# MCU.net
KiCad netlist of a schematic drawn in Altium Designer
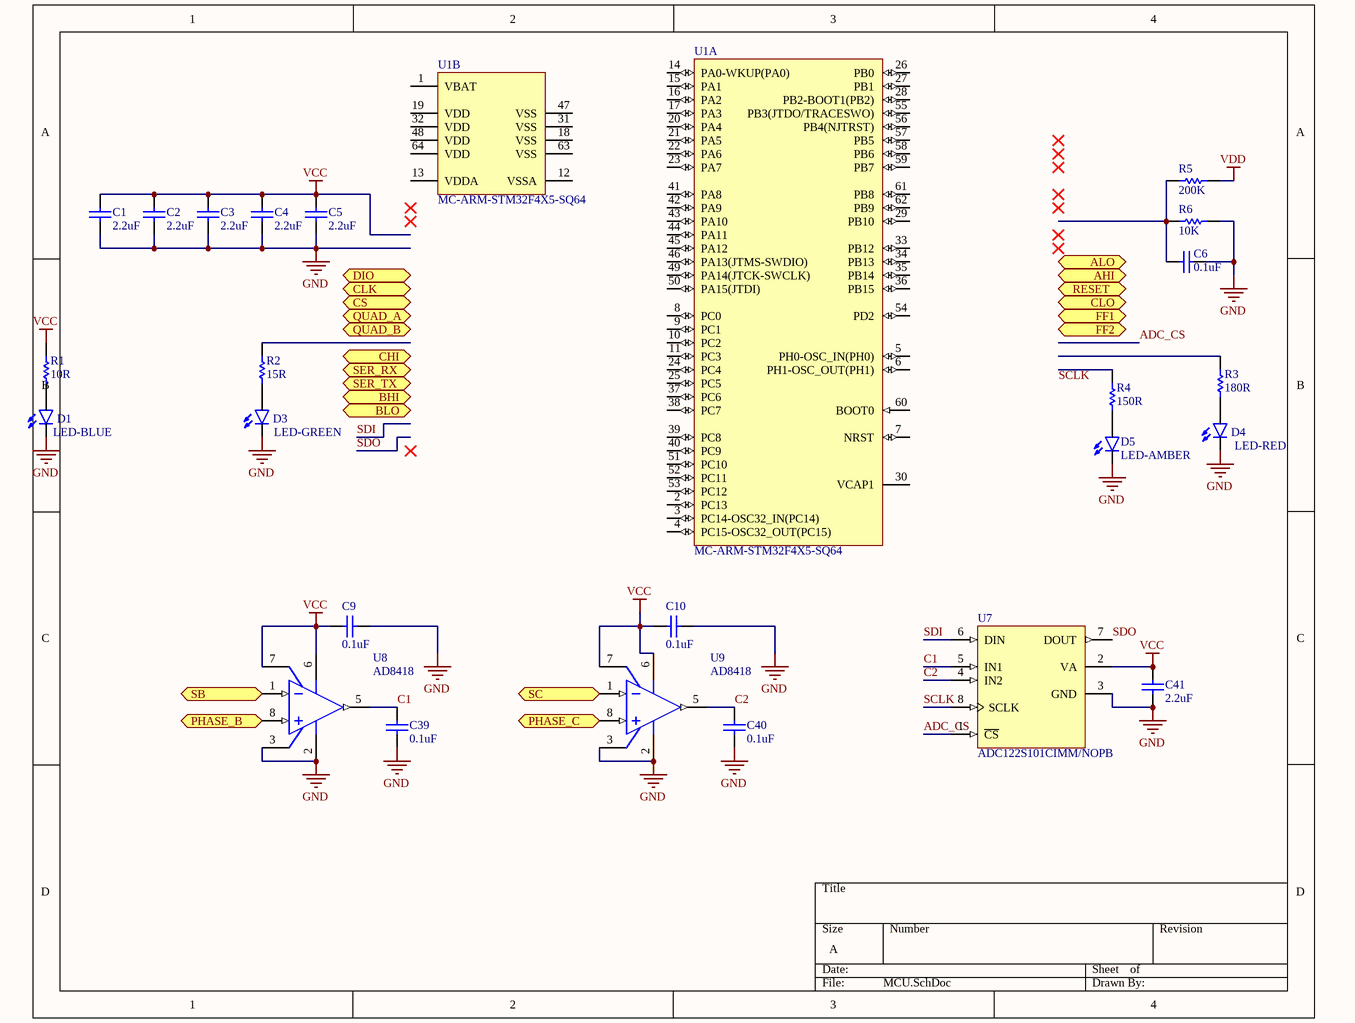
[diagram p0: MCU.SchDoc]

(export (version "E")
  (design (tool "Eeschema 10.0.6"))
  (components
    (comp (ref "C1")
      (value "2.2uF")
      (footprint "CAPC0603(1608)55_N")
      (description "CAP 2.2uF 16V Â±10% 0603 (1608 Metric) Thickness 0.55mm SMD")
      (fields (field (name "TOLERANCE") "Â±10%"))
      (libsource (lib "Altium Content Vault") (part "CMP-1035-02762-1"))
    )
    (comp (ref "C2")
      (value "2.2uF")
      (footprint "CAPC0603(1608)55_N")
      (description "CAP 2.2uF 16V Â±10% 0603 (1608 Metric) Thickness 0.55mm SMD")
      (fields (field (name "TOLERANCE") "Â±10%"))
      (libsource (lib "Altium Content Vault") (part "CMP-1035-02762-1"))
    )
    (comp (ref "C3")
      (value "2.2uF")
      (footprint "CAPC0603(1608)55_N")
      (description "CAP 2.2uF 16V Â±10% 0603 (1608 Metric) Thickness 0.55mm SMD")
      (fields (field (name "TOLERANCE") "Â±10%"))
      (libsource (lib "Altium Content Vault") (part "CMP-1035-02762-1"))
    )
    (comp (ref "C4")
      (value "2.2uF")
      (footprint "CAPC0603(1608)55_N")
      (description "CAP 2.2uF 16V Â±10% 0603 (1608 Metric) Thickness 0.55mm SMD")
      (fields (field (name "TOLERANCE") "Â±10%"))
      (libsource (lib "Altium Content Vault") (part "CMP-1035-02762-1"))
    )
    (comp (ref "C5")
      (value "2.2uF")
      (footprint "CAPC0603(1608)55_N")
      (description "CAP 2.2uF 16V Â±10% 0603 (1608 Metric) Thickness 0.55mm SMD")
      (fields (field (name "TOLERANCE") "Â±10%"))
      (libsource (lib "Altium Content Vault") (part "CMP-1035-02762-1"))
    )
    (comp (ref "C6")
      (value "0.1uF")
      (footprint "CAPC0603(1608)100_L")
      (description "CAP 100nF 50V Â±5% 0603 (1608 Metric) Thickness 1mm SMD")
      (fields (field (name "TOLERANCE") "Â±5%"))
      (libsource (lib "Altium Content Vault") (part "CMP-1035-02591-1"))
    )
    (comp (ref "C9")
      (value "0.1uF")
      (footprint "CAPC0603(1608)100_L")
      (description "CAP 100nF 6.3V Â±20% 0603 (1608 Metric) Thickness 1mm SMD")
      (fields (field (name "TOLERANCE") "Â±20%"))
      (libsource (lib "Altium Content Vault") (part "CMP-1035-02577-1"))
    )
    (comp (ref "C10")
      (value "0.1uF")
      (footprint "CAPC0603(1608)100_L")
      (description "CAP 100nF 6.3V Â±20% 0603 (1608 Metric) Thickness 1mm SMD")
      (fields (field (name "TOLERANCE") "Â±20%"))
      (libsource (lib "Altium Content Vault") (part "CMP-1035-02577-1"))
    )
    (comp (ref "C39")
      (value "0.1uF")
      (footprint "CAPC0603(1608)100_M")
      (description "CAP 100nF 6.3V ±5% 0603 (1608 Metric) Thickness 1mm SMD")
      (fields (field (name "TOLERANCE") "Â±5%"))
      (libsource (lib "Altium Content Vault") (part "CAP"))
    )
    (comp (ref "C40")
      (value "0.1uF")
      (footprint "CAPC0603(1608)100_M")
      (description "CAP 100nF 6.3V ±5% 0603 (1608 Metric) Thickness 1mm SMD")
      (fields (field (name "TOLERANCE") "Â±5%"))
      (libsource (lib "Altium Content Vault") (part "CAP"))
    )
    (comp (ref "C41")
      (value "2.2uF")
      (footprint "CAPC0603(1608)100_L")
      (description "CAP 2.2uF 6.3V ±10% 0603 (1608 Metric) Thickness 1mm SMD")
      (fields (field (name "TOLERANCE") "Â±10%"))
      (libsource (lib "Altium Content Vault") (part "CAP"))
    )
    (comp (ref "D1")
      (value "LED-BLUE")
      (footprint "LED-1206")
      (libsource (lib "Components") (part "LED-BLUE1206"))
    )
    (comp (ref "D3")
      (value "LED-GREEN")
      (footprint "LED-1206")
      (libsource (lib "Components") (part "LED-GREEN1206"))
    )
    (comp (ref "D4")
      (value "LED-RED")
      (footprint "LED-1206")
      (libsource (lib "Components") (part "LED-RED1206"))
    )
    (comp (ref "D5")
      (value "LED-AMBER")
      (footprint "LED-1206")
      (libsource (lib "Components") (part "LED-AMBER1206"))
    )
    (comp (ref "R1")
      (value "10R")
      (footprint "RESC0603(1608)_N")
      (description "10R 0.1W 5% 0603 (1608 Metric)  SMD")
      (fields (field (name "TOLERANCE") "5 %") (field (name "POWER") "0.1 W"))
      (libsource (lib "Altium Content Vault") (part "CMP-1012-00026-1"))
    )
    (comp (ref "R2")
      (value "15R")
      (footprint "RESC0603(1608)_N")
      (description "15R 0.1W 5% 0603 (1608 Metric)  SMD")
      (fields (field (name "TOLERANCE") "5 %") (field (name "POWER") "0.1 W"))
      (libsource (lib "Altium Content Vault") (part "CMP-1012-00030-1"))
    )
    (comp (ref "R3")
      (value "180R")
      (footprint "RESC0603(1608)_N")
      (description "180R 0.1W 5% 0603 (1608 Metric)  SMD")
      (fields (field (name "POWER") "0.1 W") (field (name "TOLERANCE") "5 %"))
      (libsource (lib "Altium Content Vault") (part "CMP-1012-00056-1"))
    )
    (comp (ref "R4")
      (value "150R")
      (footprint "RESC0603(1608)_N")
      (description "150R 0.1W 5% 0603 (1608 Metric)  SMD")
      (fields (field (name "POWER") "0.1 W") (field (name "TOLERANCE") "5 %"))
      (libsource (lib "Altium Content Vault") (part "CMP-1012-00054-1"))
    )
    (comp (ref "R5")
      (value "200K")
      (footprint "RESC0603(1608)_N")
      (description "200K 0.1W 5% 0603 (1608 Metric)  SMD")
      (fields (field (name "POWER") "0.1 W") (field (name "TOLERANCE") "5 %"))
      (libsource (lib "Altium Content Vault") (part "CMP-1012-00129-1"))
    )
    (comp (ref "R6")
      (value "10K")
      (footprint "RESC0603(1608)_N")
      (description "10K 0.1W 5% 0603 (1608 Metric)  SMD")
      (fields (field (name "TOLERANCE") "5 %") (field (name "POWER") "0.1 W"))
      (libsource (lib "Altium Content Vault") (part "RES"))
    )
    (comp (ref "U1")
      (value "MC-ARM-STM32F4X5-SQ64")
      (footprint "STM-LQFP64_N")
      (libsource (lib "Components") (part "MC-ARM-STM32F4X5-SQ64"))
    )
    (comp (ref "U7")
      (value "ADC122S101CIMM/NOPB")
      (footprint "MUA08A_L")
      (description "2 Channel, 500 kSPS to 1 MSPS 12-Bit A/D Converter, 8-pin Mini SOIC, Pb-Free")
      (fields (field (name "MANUFACTURER") "National Semiconductor"))
      (libsource (lib "Altium Content Vault") (part "CON-ADC-ADC102S101CIMM"))
    )
    (comp (ref "U8") (value "AD8418") (footprint "MSOP-8") (libsource (lib "Components") (part "AD8418")))
    (comp (ref "U9") (value "AD8418") (footprint "MSOP-8") (libsource (lib "Components") (part "AD8418")))
  )
  (nets
    (net (code "1") (name "/ADC_CS") (class "Default")
      (node (ref "U7") (pin "1") (pinfunction "~{CS}_1") (pintype "input"))
    )
    (net (code "6") (name "/C1") (class "Default")
      (node (ref "C39") (pin "2") (pinfunction "2_2") (pintype "passive"))
      (node (ref "U7") (pin "5") (pinfunction "IN1_5") (pintype "input"))
      (node (ref "U8") (pin "5") (pinfunction "OUT_5") (pintype "output"))
    )
    (net (code "7") (name "/C2") (class "Default")
      (node (ref "C40") (pin "2") (pinfunction "2_2") (pintype "passive"))
      (node (ref "U7") (pin "4") (pinfunction "IN2_4") (pintype "input"))
      (node (ref "U9") (pin "5") (pinfunction "OUT_5") (pintype "output"))
    )
    (net (code "15") (name "/PHASE_B") (class "Default")
      (node (ref "U8") (pin "8") (pinfunction "IN+_8") (pintype "input"))
    )
    (net (code "16") (name "/PHASE_C") (class "Default")
      (node (ref "U9") (pin "8") (pinfunction "IN+_8") (pintype "input"))
    )
    (net (code "20") (name "/SB") (class "Default")
      (node (ref "U8") (pin "1") (pinfunction "IN-_1") (pintype "input"))
    )
    (net (code "21") (name "/SC") (class "Default")
      (node (ref "U9") (pin "1") (pinfunction "IN-_1") (pintype "input"))
    )
    (net (code "22") (name "/SCLK") (class "Default")
      (node (ref "U7") (pin "8") (pinfunction "SCLK_8") (pintype "input"))
    )
    (net (code "23") (name "/SDI") (class "Default")
      (node (ref "U7") (pin "6") (pinfunction "DIN_6") (pintype "input"))
    )
    (net (code "24") (name "/SDO") (class "Default")
      (node (ref "U7") (pin "7") (pinfunction "DOUT_7") (pintype "output"))
    )
    (net (code "27") (name "GND") (class "Default")
      (node (ref "C1") (pin "1") (pinfunction "1_1") (pintype "passive"))
      (node (ref "C10") (pin "1") (pinfunction "1_1") (pintype "passive"))
      (node (ref "C2") (pin "1") (pinfunction "1_1") (pintype "passive"))
      (node (ref "C3") (pin "1") (pinfunction "1_1") (pintype "passive"))
      (node (ref "C39") (pin "1") (pinfunction "1_1") (pintype "passive"))
      (node (ref "C4") (pin "1") (pinfunction "1_1") (pintype "passive"))
      (node (ref "C40") (pin "1") (pinfunction "1_1") (pintype "passive"))
      (node (ref "C41") (pin "1") (pinfunction "1_1") (pintype "passive"))
      (node (ref "C5") (pin "1") (pinfunction "1_1") (pintype "passive"))
      (node (ref "C6") (pin "2") (pinfunction "2_2") (pintype "passive"))
      (node (ref "C9") (pin "1") (pinfunction "1_1") (pintype "passive"))
      (node (ref "D1") (pin "C") (pinfunction "C_C") (pintype "passive"))
      (node (ref "D3") (pin "C") (pinfunction "C_C") (pintype "passive"))
      (node (ref "D4") (pin "C") (pinfunction "C_C") (pintype "passive"))
      (node (ref "D5") (pin "C") (pinfunction "C_C") (pintype "passive"))
      (node (ref "R6") (pin "2") (pinfunction "2_2") (pintype "passive"))
      (node (ref "U7") (pin "3") (pinfunction "GND_3") (pintype "power_in"))
      (node (ref "U8") (pin "2") (pinfunction "GND_2") (pintype "power_in"))
      (node (ref "U8") (pin "3") (pinfunction "VREF2_3") (pintype "passive"))
      (node (ref "U9") (pin "2") (pinfunction "GND_2") (pintype "power_in"))
      (node (ref "U9") (pin "3") (pinfunction "VREF2_3") (pintype "passive"))
    )
    (net (code "28") (name "Net-(C6-Pad1)") (class "Default")
      (node (ref "C6") (pin "1") (pinfunction "1_1") (pintype "passive"))
      (node (ref "R5") (pin "1") (pinfunction "1_1") (pintype "passive"))
      (node (ref "R6") (pin "1") (pinfunction "1_1") (pintype "passive"))
    )
    (net (code "29") (name "Net-(D1-PadA)") (class "Default")
      (node (ref "D1") (pin "A") (pinfunction "A_A") (pintype "passive"))
      (node (ref "R1") (pin "1") (pinfunction "1_1") (pintype "passive"))
    )
    (net (code "30") (name "Net-(D3-PadA)") (class "Default")
      (node (ref "D3") (pin "A") (pinfunction "A_A") (pintype "passive"))
      (node (ref "R2") (pin "1") (pinfunction "1_1") (pintype "passive"))
    )
    (net (code "31") (name "Net-(D4-PadA)") (class "Default")
      (node (ref "D4") (pin "A") (pinfunction "A_A") (pintype "passive"))
      (node (ref "R3") (pin "1") (pinfunction "1_1") (pintype "passive"))
    )
    (net (code "32") (name "Net-(D5-PadA)") (class "Default")
      (node (ref "D5") (pin "A") (pinfunction "A_A") (pintype "passive"))
      (node (ref "R4") (pin "1") (pinfunction "1_1") (pintype "passive"))
    )
    (net (code "33") (name "VCC") (class "Default")
      (node (ref "C1") (pin "2") (pinfunction "2_2") (pintype "passive"))
      (node (ref "C10") (pin "2") (pinfunction "2_2") (pintype "passive"))
      (node (ref "C2") (pin "2") (pinfunction "2_2") (pintype "passive"))
      (node (ref "C3") (pin "2") (pinfunction "2_2") (pintype "passive"))
      (node (ref "C4") (pin "2") (pinfunction "2_2") (pintype "passive"))
      (node (ref "C41") (pin "2") (pinfunction "2_2") (pintype "passive"))
      (node (ref "C5") (pin "2") (pinfunction "2_2") (pintype "passive"))
      (node (ref "C9") (pin "2") (pinfunction "2_2") (pintype "passive"))
      (node (ref "R1") (pin "2") (pinfunction "2_2") (pintype "passive"))
      (node (ref "U7") (pin "2") (pinfunction "VA_2") (pintype "power_in"))
      (node (ref "U8") (pin "6") (pinfunction "VS_6") (pintype "power_in"))
      (node (ref "U8") (pin "7") (pinfunction "VREF1_7") (pintype "passive"))
      (node (ref "U9") (pin "6") (pinfunction "VS_6") (pintype "power_in"))
      (node (ref "U9") (pin "7") (pinfunction "VREF1_7") (pintype "passive"))
    )
    (net (code "34") (name "VDD") (class "Default")
      (node (ref "R5") (pin "2") (pinfunction "2_2") (pintype "passive"))
    )
    (net (code "35") (name "unconnected-(R2-Pad2)") (class "Default")
      (node (ref "R2") (pin "2") (pinfunction "2_2") (pintype "passive"))
    )
    (net (code "36") (name "unconnected-(R3-Pad2)") (class "Default")
      (node (ref "R3") (pin "2") (pinfunction "2_2") (pintype "passive"))
    )
    (net (code "37") (name "unconnected-(R4-Pad2)") (class "Default")
      (node (ref "R4") (pin "2") (pinfunction "2_2") (pintype "passive"))
    )
    (net (code "38") (name "unconnected-(U1A-BOOT0-Pad60)") (class "Default")
      (node (ref "U1") (pin "60") (pinfunction "BOOT0_60") (pintype "input"))
    )
    (net (code "39") (name "unconnected-(U1A-NRST-Pad7)") (class "Default")
      (node (ref "U1") (pin "7") (pinfunction "NRST_7") (pintype "bidirectional"))
    )
    (net (code "40") (name "unconnected-(U1A-PA0-WKUP(PA0)-Pad14)") (class "Default")
      (node (ref "U1") (pin "14") (pinfunction "PA0-WKUP(PA0)_14") (pintype "bidirectional"))
    )
    (net (code "41") (name "unconnected-(U1A-PA1-Pad15)") (class "Default")
      (node (ref "U1") (pin "15") (pinfunction "PA1_15") (pintype "bidirectional"))
    )
    (net (code "42") (name "unconnected-(U1A-PA2-Pad16)") (class "Default")
      (node (ref "U1") (pin "16") (pinfunction "PA2_16") (pintype "bidirectional"))
    )
    (net (code "43") (name "unconnected-(U1A-PA3-Pad17)") (class "Default")
      (node (ref "U1") (pin "17") (pinfunction "PA3_17") (pintype "bidirectional"))
    )
    (net (code "44") (name "unconnected-(U1A-PA4-Pad20)") (class "Default")
      (node (ref "U1") (pin "20") (pinfunction "PA4_20") (pintype "bidirectional"))
    )
    (net (code "45") (name "unconnected-(U1A-PA5-Pad21)") (class "Default")
      (node (ref "U1") (pin "21") (pinfunction "PA5_21") (pintype "bidirectional"))
    )
    (net (code "46") (name "unconnected-(U1A-PA6-Pad22)") (class "Default")
      (node (ref "U1") (pin "22") (pinfunction "PA6_22") (pintype "bidirectional"))
    )
    (net (code "47") (name "unconnected-(U1A-PA7-Pad23)") (class "Default")
      (node (ref "U1") (pin "23") (pinfunction "PA7_23") (pintype "bidirectional"))
    )
    (net (code "48") (name "unconnected-(U1A-PA8-Pad41)") (class "Default")
      (node (ref "U1") (pin "41") (pinfunction "PA8_41") (pintype "bidirectional"))
    )
    (net (code "49") (name "unconnected-(U1A-PA9-Pad42)") (class "Default")
      (node (ref "U1") (pin "42") (pinfunction "PA9_42") (pintype "bidirectional"))
    )
    (net (code "50") (name "unconnected-(U1A-PA10-Pad43)") (class "Default")
      (node (ref "U1") (pin "43") (pinfunction "PA10_43") (pintype "bidirectional"))
    )
    (net (code "51") (name "unconnected-(U1A-PA11-Pad44)") (class "Default")
      (node (ref "U1") (pin "44") (pinfunction "PA11_44") (pintype "bidirectional"))
    )
    (net (code "52") (name "unconnected-(U1A-PA12-Pad45)") (class "Default")
      (node (ref "U1") (pin "45") (pinfunction "PA12_45") (pintype "bidirectional"))
    )
    (net (code "53") (name "unconnected-(U1A-PA13(JTMS-SWDIO)-Pad46)") (class "Default")
      (node (ref "U1") (pin "46") (pinfunction "PA13(JTMS-SWDIO)_46") (pintype "bidirectional"))
    )
    (net (code "54") (name "unconnected-(U1A-PA14(JTCK-SWCLK)-Pad49)") (class "Default")
      (node (ref "U1") (pin "49") (pinfunction "PA14(JTCK-SWCLK)_49") (pintype "bidirectional"))
    )
    (net (code "55") (name "unconnected-(U1A-PA15(JTDI)-Pad50)") (class "Default")
      (node (ref "U1") (pin "50") (pinfunction "PA15(JTDI)_50") (pintype "bidirectional"))
    )
    (net (code "56") (name "unconnected-(U1A-PB0-Pad26)") (class "Default")
      (node (ref "U1") (pin "26") (pinfunction "PB0_26") (pintype "bidirectional"))
    )
    (net (code "57") (name "unconnected-(U1A-PB1-Pad27)") (class "Default")
      (node (ref "U1") (pin "27") (pinfunction "PB1_27") (pintype "bidirectional"))
    )
    (net (code "58") (name "unconnected-(U1A-PB2-BOOT1(PB2)-Pad28)") (class "Default")
      (node (ref "U1") (pin "28") (pinfunction "PB2-BOOT1(PB2)_28") (pintype "bidirectional"))
    )
    (net (code "59") (name "unconnected-(U1A-PB3(JTDO{slash}TRACESWO)-Pad55)") (class "Default")
      (node (ref "U1") (pin "55") (pinfunction "PB3(JTDO/TRACESWO)_55") (pintype "bidirectional"))
    )
    (net (code "60") (name "unconnected-(U1A-PB4(NJTRST)-Pad56)") (class "Default")
      (node (ref "U1") (pin "56") (pinfunction "PB4(NJTRST)_56") (pintype "bidirectional"))
    )
    (net (code "61") (name "unconnected-(U1A-PB5-Pad57)") (class "Default")
      (node (ref "U1") (pin "57") (pinfunction "PB5_57") (pintype "bidirectional"))
    )
    (net (code "62") (name "unconnected-(U1A-PB6-Pad58)") (class "Default")
      (node (ref "U1") (pin "58") (pinfunction "PB6_58") (pintype "bidirectional"))
    )
    (net (code "63") (name "unconnected-(U1A-PB7-Pad59)") (class "Default")
      (node (ref "U1") (pin "59") (pinfunction "PB7_59") (pintype "bidirectional"))
    )
    (net (code "64") (name "unconnected-(U1A-PB8-Pad61)") (class "Default")
      (node (ref "U1") (pin "61") (pinfunction "PB8_61") (pintype "bidirectional"))
    )
    (net (code "65") (name "unconnected-(U1A-PB9-Pad62)") (class "Default")
      (node (ref "U1") (pin "62") (pinfunction "PB9_62") (pintype "bidirectional"))
    )
    (net (code "66") (name "unconnected-(U1A-PB10-Pad29)") (class "Default")
      (node (ref "U1") (pin "29") (pinfunction "PB10_29") (pintype "bidirectional"))
    )
    (net (code "67") (name "unconnected-(U1A-PB12-Pad33)") (class "Default")
      (node (ref "U1") (pin "33") (pinfunction "PB12_33") (pintype "bidirectional"))
    )
    (net (code "68") (name "unconnected-(U1A-PB13-Pad34)") (class "Default")
      (node (ref "U1") (pin "34") (pinfunction "PB13_34") (pintype "bidirectional"))
    )
    (net (code "69") (name "unconnected-(U1A-PB14-Pad35)") (class "Default")
      (node (ref "U1") (pin "35") (pinfunction "PB14_35") (pintype "bidirectional"))
    )
    (net (code "70") (name "unconnected-(U1A-PB15-Pad36)") (class "Default")
      (node (ref "U1") (pin "36") (pinfunction "PB15_36") (pintype "bidirectional"))
    )
    (net (code "71") (name "unconnected-(U1A-PC0-Pad8)") (class "Default")
      (node (ref "U1") (pin "8") (pinfunction "PC0_8") (pintype "bidirectional"))
    )
    (net (code "72") (name "unconnected-(U1A-PC1-Pad9)") (class "Default")
      (node (ref "U1") (pin "9") (pinfunction "PC1_9") (pintype "bidirectional"))
    )
    (net (code "73") (name "unconnected-(U1A-PC2-Pad10)") (class "Default")
      (node (ref "U1") (pin "10") (pinfunction "PC2_10") (pintype "bidirectional"))
    )
    (net (code "74") (name "unconnected-(U1A-PC3-Pad11)") (class "Default")
      (node (ref "U1") (pin "11") (pinfunction "PC3_11") (pintype "bidirectional"))
    )
    (net (code "75") (name "unconnected-(U1A-PC4-Pad24)") (class "Default")
      (node (ref "U1") (pin "24") (pinfunction "PC4_24") (pintype "bidirectional"))
    )
    (net (code "76") (name "unconnected-(U1A-PC5-Pad25)") (class "Default")
      (node (ref "U1") (pin "25") (pinfunction "PC5_25") (pintype "bidirectional"))
    )
    (net (code "77") (name "unconnected-(U1A-PC6-Pad37)") (class "Default")
      (node (ref "U1") (pin "37") (pinfunction "PC6_37") (pintype "bidirectional"))
    )
    (net (code "78") (name "unconnected-(U1A-PC7-Pad38)") (class "Default")
      (node (ref "U1") (pin "38") (pinfunction "PC7_38") (pintype "bidirectional"))
    )
    (net (code "79") (name "unconnected-(U1A-PC8-Pad39)") (class "Default")
      (node (ref "U1") (pin "39") (pinfunction "PC8_39") (pintype "bidirectional"))
    )
    (net (code "80") (name "unconnected-(U1A-PC9-Pad40)") (class "Default")
      (node (ref "U1") (pin "40") (pinfunction "PC9_40") (pintype "bidirectional"))
    )
    (net (code "81") (name "unconnected-(U1A-PC10-Pad51)") (class "Default")
      (node (ref "U1") (pin "51") (pinfunction "PC10_51") (pintype "bidirectional"))
    )
    (net (code "82") (name "unconnected-(U1A-PC11-Pad52)") (class "Default")
      (node (ref "U1") (pin "52") (pinfunction "PC11_52") (pintype "bidirectional"))
    )
    (net (code "83") (name "unconnected-(U1A-PC12-Pad53)") (class "Default")
      (node (ref "U1") (pin "53") (pinfunction "PC12_53") (pintype "bidirectional"))
    )
    (net (code "84") (name "unconnected-(U1A-PC13-Pad2)") (class "Default")
      (node (ref "U1") (pin "2") (pinfunction "PC13_2") (pintype "bidirectional"))
    )
    (net (code "85") (name "unconnected-(U1A-PC14-OSC32_IN(PC14)-Pad3)") (class "Default")
      (node (ref "U1") (pin "3") (pinfunction "PC14-OSC32_IN(PC14)_3") (pintype "bidirectional"))
    )
    (net (code "86") (name "unconnected-(U1A-PC15-OSC32_OUT(PC15)-Pad4)") (class "Default")
      (node (ref "U1") (pin "4") (pinfunction "PC15-OSC32_OUT(PC15)_4") (pintype "bidirectional"))
    )
    (net (code "87") (name "unconnected-(U1A-PD2-Pad54)") (class "Default")
      (node (ref "U1") (pin "54") (pinfunction "PD2_54") (pintype "bidirectional"))
    )
    (net (code "88") (name "unconnected-(U1A-PH0-OSC_IN(PH0)-Pad5)") (class "Default")
      (node (ref "U1") (pin "5") (pinfunction "PH0-OSC_IN(PH0)_5") (pintype "bidirectional"))
    )
    (net (code "89") (name "unconnected-(U1A-PH1-OSC_OUT(PH1)-Pad6)") (class "Default")
      (node (ref "U1") (pin "6") (pinfunction "PH1-OSC_OUT(PH1)_6") (pintype "bidirectional"))
    )
    (net (code "90") (name "unconnected-(U1A-VCAP1-Pad30)") (class "Default")
      (node (ref "U1") (pin "30") (pinfunction "VCAP1_30") (pintype "power_in"))
    )
    (net (code "91") (name "unconnected-(U1B-VBAT-Pad1)") (class "Default")
      (node (ref "U1") (pin "1") (pinfunction "VBAT_1") (pintype "power_in"))
    )
    (net (code "92") (name "unconnected-(U1B-VDD-Pad19)") (class "Default")
      (node (ref "U1") (pin "19") (pinfunction "VDD_19") (pintype "power_in"))
    )
    (net (code "93") (name "unconnected-(U1B-VDD-Pad32)") (class "Default")
      (node (ref "U1") (pin "32") (pinfunction "VDD_32") (pintype "power_in"))
    )
    (net (code "94") (name "unconnected-(U1B-VDD-Pad48)") (class "Default")
      (node (ref "U1") (pin "48") (pinfunction "VDD_48") (pintype "power_in"))
    )
    (net (code "95") (name "unconnected-(U1B-VDD-Pad64)") (class "Default")
      (node (ref "U1") (pin "64") (pinfunction "VDD_64") (pintype "power_in"))
    )
    (net (code "96") (name "unconnected-(U1B-VDDA-Pad13)") (class "Default")
      (node (ref "U1") (pin "13") (pinfunction "VDDA_13") (pintype "power_in"))
    )
    (net (code "97") (name "unconnected-(U1B-VSS-Pad18)") (class "Default")
      (node (ref "U1") (pin "18") (pinfunction "VSS_18") (pintype "power_in"))
    )
    (net (code "98") (name "unconnected-(U1B-VSS-Pad31)") (class "Default")
      (node (ref "U1") (pin "31") (pinfunction "VSS_31") (pintype "power_in"))
    )
    (net (code "99") (name "unconnected-(U1B-VSS-Pad47)") (class "Default")
      (node (ref "U1") (pin "47") (pinfunction "VSS_47") (pintype "power_in"))
    )
    (net (code "100") (name "unconnected-(U1B-VSS-Pad63)") (class "Default")
      (node (ref "U1") (pin "63") (pinfunction "VSS_63") (pintype "power_in"))
    )
    (net (code "101") (name "unconnected-(U1B-VSSA-Pad12)") (class "Default")
      (node (ref "U1") (pin "12") (pinfunction "VSSA_12") (pintype "power_in"))
    )
  )
)
